# NTC.net
KiCad netlist of a schematic drawn in Altium Designer
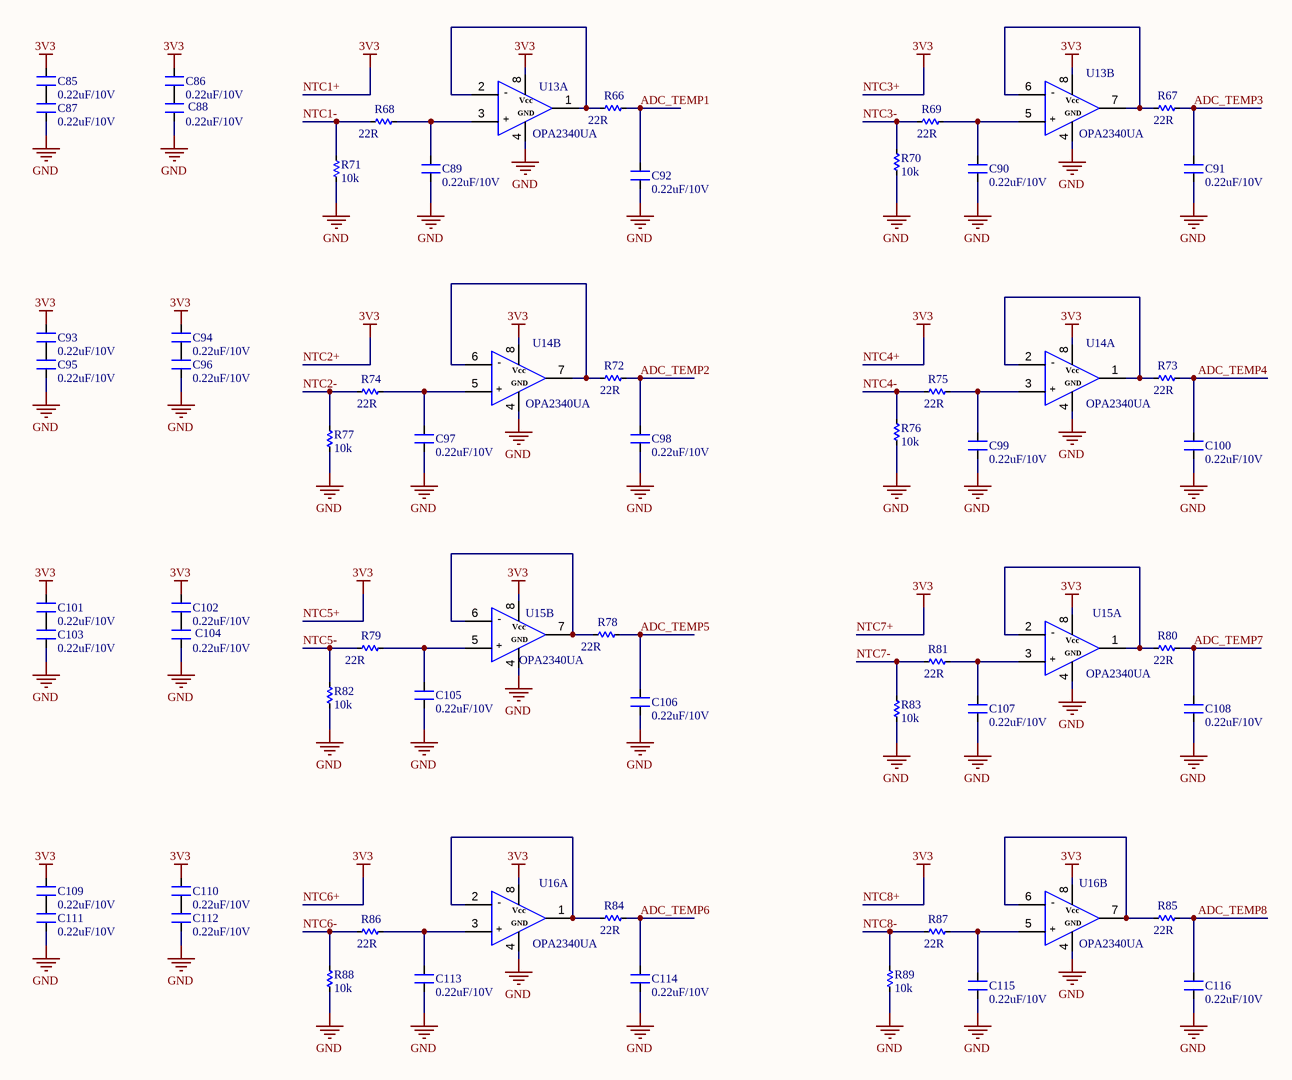
[diagram p0: NTC.SchDoc]

(export (version "E")
  (design (tool "Eeschema 10.0.6"))
  (components
    (comp (ref "C85")
      (value "0.22uF/10V")
      (footprint "CAP_C_1608X80")
      (libsource (lib "EXP_HW_V3") (part "Capacitors"))
    )
    (comp (ref "C86")
      (value "0.22uF/10V")
      (footprint "CAP_C_1608X80")
      (libsource (lib "EXP_HW_V3") (part "Capacitors"))
    )
    (comp (ref "C87")
      (value "0.22uF/10V")
      (footprint "CAP_C_1608X80")
      (libsource (lib "EXP_HW_V3") (part "Capacitors"))
    )
    (comp (ref "C88")
      (value "0.22uF/10V")
      (footprint "CAP_C_1608X80")
      (libsource (lib "EXP_HW_V3") (part "Capacitors"))
    )
    (comp (ref "C89")
      (value "0.22uF/10V")
      (footprint "CAP_C_1608X80")
      (libsource (lib "EXP_HW_V3") (part "Capacitors"))
    )
    (comp (ref "C90")
      (value "0.22uF/10V")
      (footprint "CAP_C_1608X80")
      (libsource (lib "EXP_HW_V3") (part "Capacitors"))
    )
    (comp (ref "C91")
      (value "0.22uF/10V")
      (footprint "CAP_C_1608X80")
      (libsource (lib "EXP_HW_V3") (part "Capacitors"))
    )
    (comp (ref "C92")
      (value "0.22uF/10V")
      (footprint "CAP_C_1608X80")
      (libsource (lib "EXP_HW_V3") (part "Capacitors"))
    )
    (comp (ref "C93")
      (value "0.22uF/10V")
      (footprint "CAP_C_1608X80")
      (libsource (lib "EXP_HW_V3") (part "Capacitors"))
    )
    (comp (ref "C94")
      (value "0.22uF/10V")
      (footprint "CAP_C_1608X80")
      (libsource (lib "EXP_HW_V3") (part "Capacitors"))
    )
    (comp (ref "C95")
      (value "0.22uF/10V")
      (footprint "CAP_C_1608X80")
      (libsource (lib "EXP_HW_V3") (part "Capacitors"))
    )
    (comp (ref "C96")
      (value "0.22uF/10V")
      (footprint "CAP_C_1608X80")
      (libsource (lib "EXP_HW_V3") (part "Capacitors"))
    )
    (comp (ref "C97")
      (value "0.22uF/10V")
      (footprint "CAP_C_1608X80")
      (libsource (lib "EXP_HW_V3") (part "Capacitors"))
    )
    (comp (ref "C98")
      (value "0.22uF/10V")
      (footprint "CAP_C_1608X80")
      (libsource (lib "EXP_HW_V3") (part "Capacitors"))
    )
    (comp (ref "C99")
      (value "0.22uF/10V")
      (footprint "CAP_C_1608X80")
      (libsource (lib "EXP_HW_V3") (part "Capacitors"))
    )
    (comp (ref "C100")
      (value "0.22uF/10V")
      (footprint "CAP_C_1608X80")
      (libsource (lib "EXP_HW_V3") (part "Capacitors"))
    )
    (comp (ref "C101")
      (value "0.22uF/10V")
      (footprint "CAP_C_1608X80")
      (libsource (lib "EXP_HW_V3") (part "Capacitors"))
    )
    (comp (ref "C102")
      (value "0.22uF/10V")
      (footprint "CAP_C_1608X80")
      (libsource (lib "EXP_HW_V3") (part "Capacitors"))
    )
    (comp (ref "C103")
      (value "0.22uF/10V")
      (footprint "CAP_C_1608X80")
      (libsource (lib "EXP_HW_V3") (part "Capacitors"))
    )
    (comp (ref "C104")
      (value "0.22uF/10V")
      (footprint "CAP_C_1608X80")
      (libsource (lib "EXP_HW_V3") (part "Capacitors"))
    )
    (comp (ref "C105")
      (value "0.22uF/10V")
      (footprint "CAP_C_1608X80")
      (libsource (lib "EXP_HW_V3") (part "Capacitors"))
    )
    (comp (ref "C106")
      (value "0.22uF/10V")
      (footprint "CAP_C_1608X80")
      (libsource (lib "EXP_HW_V3") (part "Capacitors"))
    )
    (comp (ref "C107")
      (value "0.22uF/10V")
      (footprint "CAP_C_1608X80")
      (libsource (lib "EXP_HW_V3") (part "Capacitors"))
    )
    (comp (ref "C108")
      (value "0.22uF/10V")
      (footprint "CAP_C_1608X80")
      (libsource (lib "EXP_HW_V3") (part "Capacitors"))
    )
    (comp (ref "C109")
      (value "0.22uF/10V")
      (footprint "CAP_C_1608X80")
      (libsource (lib "EXP_HW_V3") (part "Capacitors"))
    )
    (comp (ref "C110")
      (value "0.22uF/10V")
      (footprint "CAP_C_1608X80")
      (libsource (lib "EXP_HW_V3") (part "Capacitors"))
    )
    (comp (ref "C111")
      (value "0.22uF/10V")
      (footprint "CAP_C_1608X80")
      (libsource (lib "EXP_HW_V3") (part "Capacitors"))
    )
    (comp (ref "C112")
      (value "0.22uF/10V")
      (footprint "CAP_C_1608X80")
      (libsource (lib "EXP_HW_V3") (part "Capacitors"))
    )
    (comp (ref "C113")
      (value "0.22uF/10V")
      (footprint "CAP_C_1608X80")
      (libsource (lib "EXP_HW_V3") (part "Capacitors"))
    )
    (comp (ref "C114")
      (value "0.22uF/10V")
      (footprint "CAP_C_1608X80")
      (libsource (lib "EXP_HW_V3") (part "Capacitors"))
    )
    (comp (ref "C115")
      (value "0.22uF/10V")
      (footprint "CAP_C_1608X80")
      (libsource (lib "EXP_HW_V3") (part "Capacitors"))
    )
    (comp (ref "C116")
      (value "0.22uF/10V")
      (footprint "CAP_C_1608X80")
      (libsource (lib "EXP_HW_V3") (part "Capacitors"))
    )
    (comp (ref "R66")
      (value "22R")
      (footprint "RES_C_1608X60")
      (description "SMD")
      (fields
        (field (name "MANUFACTURER") "Generic Components")
        (field (name "PUBLISHER") "Altium Hobart Technology Centre")
      )
      (libsource (lib "EXP_HW_V3") (part "Res SMD"))
    )
    (comp (ref "R67")
      (value "22R")
      (footprint "RES_C_1608X60")
      (description "SMD")
      (fields
        (field (name "MANUFACTURER") "Generic Components")
        (field (name "PUBLISHER") "Altium Hobart Technology Centre")
      )
      (libsource (lib "EXP_HW_V3") (part "Res SMD"))
    )
    (comp (ref "R68")
      (value "22R")
      (footprint "RES_C_1608X60")
      (description "SMD")
      (fields
        (field (name "MANUFACTURER") "Generic Components")
        (field (name "PUBLISHER") "Altium Hobart Technology Centre")
      )
      (libsource (lib "EXP_HW_V3") (part "Res SMD"))
    )
    (comp (ref "R69")
      (value "22R")
      (footprint "RES_C_1608X60")
      (description "SMD")
      (fields
        (field (name "MANUFACTURER") "Generic Components")
        (field (name "PUBLISHER") "Altium Hobart Technology Centre")
      )
      (libsource (lib "EXP_HW_V3") (part "Res SMD"))
    )
    (comp (ref "R70")
      (value "10k")
      (footprint "RES_C_1608X60")
      (description "SMD")
      (fields
        (field (name "MANUFACTURER") "Generic Components")
        (field (name "PUBLISHER") "Altium Hobart Technology Centre")
      )
      (libsource (lib "EXP_HW_V3") (part "Res SMD"))
    )
    (comp (ref "R71")
      (value "10k")
      (footprint "RES_C_1608X60")
      (description "SMD")
      (fields
        (field (name "MANUFACTURER") "Generic Components")
        (field (name "PUBLISHER") "Altium Hobart Technology Centre")
      )
      (libsource (lib "EXP_HW_V3") (part "Res SMD"))
    )
    (comp (ref "R72")
      (value "22R")
      (footprint "RES_C_1608X60")
      (description "SMD")
      (fields
        (field (name "MANUFACTURER") "Generic Components")
        (field (name "PUBLISHER") "Altium Hobart Technology Centre")
      )
      (libsource (lib "EXP_HW_V3") (part "Res SMD"))
    )
    (comp (ref "R73")
      (value "22R")
      (footprint "RES_C_1608X60")
      (description "SMD")
      (fields
        (field (name "MANUFACTURER") "Generic Components")
        (field (name "PUBLISHER") "Altium Hobart Technology Centre")
      )
      (libsource (lib "EXP_HW_V3") (part "Res SMD"))
    )
    (comp (ref "R74")
      (value "22R")
      (footprint "RES_C_1608X60")
      (description "SMD")
      (fields
        (field (name "MANUFACTURER") "Generic Components")
        (field (name "PUBLISHER") "Altium Hobart Technology Centre")
      )
      (libsource (lib "EXP_HW_V3") (part "Res SMD"))
    )
    (comp (ref "R75")
      (value "22R")
      (footprint "RES_C_1608X60")
      (description "SMD")
      (fields
        (field (name "MANUFACTURER") "Generic Components")
        (field (name "PUBLISHER") "Altium Hobart Technology Centre")
      )
      (libsource (lib "EXP_HW_V3") (part "Res SMD"))
    )
    (comp (ref "R76")
      (value "10k")
      (footprint "RES_C_1608X60")
      (description "SMD")
      (fields
        (field (name "MANUFACTURER") "Generic Components")
        (field (name "PUBLISHER") "Altium Hobart Technology Centre")
      )
      (libsource (lib "EXP_HW_V3") (part "Res SMD"))
    )
    (comp (ref "R77")
      (value "10k")
      (footprint "RES_C_1608X60")
      (description "SMD")
      (fields
        (field (name "MANUFACTURER") "Generic Components")
        (field (name "PUBLISHER") "Altium Hobart Technology Centre")
      )
      (libsource (lib "EXP_HW_V3") (part "Res SMD"))
    )
    (comp (ref "R78")
      (value "22R")
      (footprint "RES_C_1608X60")
      (description "SMD")
      (fields
        (field (name "MANUFACTURER") "Generic Components")
        (field (name "PUBLISHER") "Altium Hobart Technology Centre")
      )
      (libsource (lib "EXP_HW_V3") (part "Res SMD"))
    )
    (comp (ref "R79")
      (value "22R")
      (footprint "RES_C_1608X60")
      (description "SMD")
      (fields
        (field (name "MANUFACTURER") "Generic Components")
        (field (name "PUBLISHER") "Altium Hobart Technology Centre")
      )
      (libsource (lib "EXP_HW_V3") (part "Res SMD"))
    )
    (comp (ref "R80")
      (value "22R")
      (footprint "RES_C_1608X60")
      (description "SMD")
      (fields
        (field (name "MANUFACTURER") "Generic Components")
        (field (name "PUBLISHER") "Altium Hobart Technology Centre")
      )
      (libsource (lib "EXP_HW_V3") (part "Res SMD"))
    )
    (comp (ref "R81")
      (value "22R")
      (footprint "RES_C_1608X60")
      (description "SMD")
      (fields
        (field (name "MANUFACTURER") "Generic Components")
        (field (name "PUBLISHER") "Altium Hobart Technology Centre")
      )
      (libsource (lib "EXP_HW_V3") (part "Res SMD"))
    )
    (comp (ref "R82")
      (value "10k")
      (footprint "RES_C_1608X60")
      (description "SMD")
      (fields
        (field (name "MANUFACTURER") "Generic Components")
        (field (name "PUBLISHER") "Altium Hobart Technology Centre")
      )
      (libsource (lib "EXP_HW_V3") (part "Res SMD"))
    )
    (comp (ref "R83")
      (value "10k")
      (footprint "RES_C_1608X60")
      (description "SMD")
      (fields
        (field (name "MANUFACTURER") "Generic Components")
        (field (name "PUBLISHER") "Altium Hobart Technology Centre")
      )
      (libsource (lib "EXP_HW_V3") (part "Res SMD"))
    )
    (comp (ref "R84")
      (value "22R")
      (footprint "RES_C_1608X60")
      (description "SMD")
      (fields
        (field (name "MANUFACTURER") "Generic Components")
        (field (name "PUBLISHER") "Altium Hobart Technology Centre")
      )
      (libsource (lib "EXP_HW_V3") (part "Res SMD"))
    )
    (comp (ref "R85")
      (value "22R")
      (footprint "RES_C_1608X60")
      (description "SMD")
      (fields
        (field (name "MANUFACTURER") "Generic Components")
        (field (name "PUBLISHER") "Altium Hobart Technology Centre")
      )
      (libsource (lib "EXP_HW_V3") (part "Res SMD"))
    )
    (comp (ref "R86")
      (value "22R")
      (footprint "RES_C_1608X60")
      (description "SMD")
      (fields
        (field (name "MANUFACTURER") "Generic Components")
        (field (name "PUBLISHER") "Altium Hobart Technology Centre")
      )
      (libsource (lib "EXP_HW_V3") (part "Res SMD"))
    )
    (comp (ref "R87")
      (value "22R")
      (footprint "RES_C_1608X60")
      (description "SMD")
      (fields
        (field (name "MANUFACTURER") "Generic Components")
        (field (name "PUBLISHER") "Altium Hobart Technology Centre")
      )
      (libsource (lib "EXP_HW_V3") (part "Res SMD"))
    )
    (comp (ref "R88")
      (value "10k")
      (footprint "RES_C_1608X60")
      (description "SMD")
      (fields
        (field (name "MANUFACTURER") "Generic Components")
        (field (name "PUBLISHER") "Altium Hobart Technology Centre")
      )
      (libsource (lib "EXP_HW_V3") (part "Res SMD"))
    )
    (comp (ref "R89")
      (value "10k")
      (footprint "RES_C_1608X60")
      (description "SMD")
      (fields
        (field (name "MANUFACTURER") "Generic Components")
        (field (name "PUBLISHER") "Altium Hobart Technology Centre")
      )
      (libsource (lib "EXP_HW_V3") (part "Res SMD"))
    )
    (comp (ref "U13") (value "OPA2340UA") (footprint "SO8") (libsource (lib "EXP_HW_V3") (part "OPA2340UA")))
    (comp (ref "U14") (value "OPA2340UA") (footprint "SO8") (libsource (lib "EXP_HW_V3") (part "OPA2340UA")))
    (comp (ref "U15") (value "OPA2340UA") (footprint "SO8") (libsource (lib "EXP_HW_V3") (part "OPA2340UA")))
    (comp (ref "U16") (value "OPA2340UA") (footprint "SO8") (libsource (lib "EXP_HW_V3") (part "OPA2340UA")))
  )
  (nets
    (net (code "1") (name "/ADC_TEMP1") (class "Default")
      (node (ref "C92") (pin "2") (pinfunction "2_2") (pintype "passive"))
      (node (ref "R66") (pin "2") (pinfunction "2_2") (pintype "passive"))
    )
    (net (code "2") (name "/ADC_TEMP2") (class "Default")
      (node (ref "C98") (pin "2") (pinfunction "2_2") (pintype "passive"))
      (node (ref "R72") (pin "2") (pinfunction "2_2") (pintype "passive"))
    )
    (net (code "3") (name "/ADC_TEMP3") (class "Default")
      (node (ref "C91") (pin "2") (pinfunction "2_2") (pintype "passive"))
      (node (ref "R67") (pin "2") (pinfunction "2_2") (pintype "passive"))
    )
    (net (code "4") (name "/ADC_TEMP4") (class "Default")
      (node (ref "C100") (pin "2") (pinfunction "2_2") (pintype "passive"))
      (node (ref "R73") (pin "2") (pinfunction "2_2") (pintype "passive"))
    )
    (net (code "5") (name "/ADC_TEMP5") (class "Default")
      (node (ref "C106") (pin "2") (pinfunction "2_2") (pintype "passive"))
      (node (ref "R78") (pin "2") (pinfunction "2_2") (pintype "passive"))
    )
    (net (code "6") (name "/ADC_TEMP6") (class "Default")
      (node (ref "C114") (pin "2") (pinfunction "2_2") (pintype "passive"))
      (node (ref "R84") (pin "2") (pinfunction "2_2") (pintype "passive"))
    )
    (net (code "7") (name "/ADC_TEMP7") (class "Default")
      (node (ref "C108") (pin "2") (pinfunction "2_2") (pintype "passive"))
      (node (ref "R80") (pin "2") (pinfunction "2_2") (pintype "passive"))
    )
    (net (code "8") (name "/ADC_TEMP8") (class "Default")
      (node (ref "C116") (pin "2") (pinfunction "2_2") (pintype "passive"))
      (node (ref "R85") (pin "2") (pinfunction "2_2") (pintype "passive"))
    )
    (net (code "9") (name "/NTC1-") (class "Default")
      (node (ref "R68") (pin "1") (pinfunction "1_1") (pintype "passive"))
      (node (ref "R71") (pin "1") (pinfunction "1_1") (pintype "passive"))
    )
    (net (code "10") (name "/NTC2-") (class "Default")
      (node (ref "R74") (pin "1") (pinfunction "1_1") (pintype "passive"))
      (node (ref "R77") (pin "1") (pinfunction "1_1") (pintype "passive"))
    )
    (net (code "11") (name "/NTC3-") (class "Default")
      (node (ref "R69") (pin "1") (pinfunction "1_1") (pintype "passive"))
      (node (ref "R70") (pin "1") (pinfunction "1_1") (pintype "passive"))
    )
    (net (code "12") (name "/NTC4-") (class "Default")
      (node (ref "R75") (pin "1") (pinfunction "1_1") (pintype "passive"))
      (node (ref "R76") (pin "1") (pinfunction "1_1") (pintype "passive"))
    )
    (net (code "13") (name "/NTC5-") (class "Default")
      (node (ref "R79") (pin "1") (pinfunction "1_1") (pintype "passive"))
      (node (ref "R82") (pin "1") (pinfunction "1_1") (pintype "passive"))
    )
    (net (code "14") (name "/NTC6-") (class "Default")
      (node (ref "R86") (pin "1") (pinfunction "1_1") (pintype "passive"))
      (node (ref "R88") (pin "1") (pinfunction "1_1") (pintype "passive"))
    )
    (net (code "15") (name "/NTC7-") (class "Default")
      (node (ref "R81") (pin "1") (pinfunction "1_1") (pintype "passive"))
      (node (ref "R83") (pin "1") (pinfunction "1_1") (pintype "passive"))
    )
    (net (code "16") (name "/NTC8-") (class "Default")
      (node (ref "R87") (pin "1") (pinfunction "1_1") (pintype "passive"))
      (node (ref "R89") (pin "1") (pinfunction "1_1") (pintype "passive"))
    )
    (net (code "17") (name "3V3") (class "Default")
      (node (ref "C101") (pin "2") (pinfunction "2_2") (pintype "passive"))
      (node (ref "C102") (pin "2") (pinfunction "2_2") (pintype "passive"))
      (node (ref "C109") (pin "2") (pinfunction "2_2") (pintype "passive"))
      (node (ref "C110") (pin "2") (pinfunction "2_2") (pintype "passive"))
      (node (ref "C85") (pin "2") (pinfunction "2_2") (pintype "passive"))
      (node (ref "C86") (pin "2") (pinfunction "2_2") (pintype "passive"))
      (node (ref "C93") (pin "2") (pinfunction "2_2") (pintype "passive"))
      (node (ref "C94") (pin "2") (pinfunction "2_2") (pintype "passive"))
      (node (ref "U13") (pin "8") (pinfunction "8_8") (pintype "passive"))
      (node (ref "U14") (pin "8") (pinfunction "8_8") (pintype "passive"))
      (node (ref "U15") (pin "8") (pinfunction "8_8") (pintype "passive"))
      (node (ref "U16") (pin "8") (pinfunction "8_8") (pintype "passive"))
    )
    (net (code "18") (name "GND") (class "Default")
      (node (ref "C100") (pin "1") (pinfunction "1_1") (pintype "passive"))
      (node (ref "C103") (pin "1") (pinfunction "1_1") (pintype "passive"))
      (node (ref "C104") (pin "1") (pinfunction "1_1") (pintype "passive"))
      (node (ref "C105") (pin "1") (pinfunction "1_1") (pintype "passive"))
      (node (ref "C106") (pin "1") (pinfunction "1_1") (pintype "passive"))
      (node (ref "C107") (pin "1") (pinfunction "1_1") (pintype "passive"))
      (node (ref "C108") (pin "1") (pinfunction "1_1") (pintype "passive"))
      (node (ref "C111") (pin "1") (pinfunction "1_1") (pintype "passive"))
      (node (ref "C112") (pin "1") (pinfunction "1_1") (pintype "passive"))
      (node (ref "C113") (pin "1") (pinfunction "1_1") (pintype "passive"))
      (node (ref "C114") (pin "1") (pinfunction "1_1") (pintype "passive"))
      (node (ref "C115") (pin "1") (pinfunction "1_1") (pintype "passive"))
      (node (ref "C116") (pin "1") (pinfunction "1_1") (pintype "passive"))
      (node (ref "C87") (pin "1") (pinfunction "1_1") (pintype "passive"))
      (node (ref "C88") (pin "1") (pinfunction "1_1") (pintype "passive"))
      (node (ref "C89") (pin "1") (pinfunction "1_1") (pintype "passive"))
      (node (ref "C90") (pin "1") (pinfunction "1_1") (pintype "passive"))
      (node (ref "C91") (pin "1") (pinfunction "1_1") (pintype "passive"))
      (node (ref "C92") (pin "1") (pinfunction "1_1") (pintype "passive"))
      (node (ref "C95") (pin "1") (pinfunction "1_1") (pintype "passive"))
      (node (ref "C96") (pin "1") (pinfunction "1_1") (pintype "passive"))
      (node (ref "C97") (pin "1") (pinfunction "1_1") (pintype "passive"))
      (node (ref "C98") (pin "1") (pinfunction "1_1") (pintype "passive"))
      (node (ref "C99") (pin "1") (pinfunction "1_1") (pintype "passive"))
      (node (ref "R70") (pin "2") (pinfunction "2_2") (pintype "passive"))
      (node (ref "R71") (pin "2") (pinfunction "2_2") (pintype "passive"))
      (node (ref "R76") (pin "2") (pinfunction "2_2") (pintype "passive"))
      (node (ref "R77") (pin "2") (pinfunction "2_2") (pintype "passive"))
      (node (ref "R82") (pin "2") (pinfunction "2_2") (pintype "passive"))
      (node (ref "R83") (pin "2") (pinfunction "2_2") (pintype "passive"))
      (node (ref "R88") (pin "2") (pinfunction "2_2") (pintype "passive"))
      (node (ref "R89") (pin "2") (pinfunction "2_2") (pintype "passive"))
      (node (ref "U13") (pin "4") (pinfunction "4_4") (pintype "passive"))
      (node (ref "U14") (pin "4") (pinfunction "4_4") (pintype "passive"))
      (node (ref "U15") (pin "4") (pinfunction "4_4") (pintype "passive"))
      (node (ref "U16") (pin "4") (pinfunction "4_4") (pintype "passive"))
    )
    (net (code "19") (name "Net-(C85-Pad1)") (class "Default")
      (node (ref "C85") (pin "1") (pinfunction "1_1") (pintype "passive"))
      (node (ref "C87") (pin "2") (pinfunction "2_2") (pintype "passive"))
    )
    (net (code "20") (name "Net-(C86-Pad1)") (class "Default")
      (node (ref "C86") (pin "1") (pinfunction "1_1") (pintype "passive"))
      (node (ref "C88") (pin "2") (pinfunction "2_2") (pintype "passive"))
    )
    (net (code "21") (name "Net-(C89-Pad2)") (class "Default")
      (node (ref "C89") (pin "2") (pinfunction "2_2") (pintype "passive"))
      (node (ref "R68") (pin "2") (pinfunction "2_2") (pintype "passive"))
      (node (ref "U13") (pin "3") (pinfunction "3_3") (pintype "passive"))
    )
    (net (code "22") (name "Net-(C90-Pad2)") (class "Default")
      (node (ref "C90") (pin "2") (pinfunction "2_2") (pintype "passive"))
      (node (ref "R69") (pin "2") (pinfunction "2_2") (pintype "passive"))
      (node (ref "U13") (pin "5") (pinfunction "5_5") (pintype "passive"))
    )
    (net (code "23") (name "Net-(C93-Pad1)") (class "Default")
      (node (ref "C93") (pin "1") (pinfunction "1_1") (pintype "passive"))
      (node (ref "C95") (pin "2") (pinfunction "2_2") (pintype "passive"))
    )
    (net (code "24") (name "Net-(C94-Pad1)") (class "Default")
      (node (ref "C94") (pin "1") (pinfunction "1_1") (pintype "passive"))
      (node (ref "C96") (pin "2") (pinfunction "2_2") (pintype "passive"))
    )
    (net (code "25") (name "Net-(C97-Pad2)") (class "Default")
      (node (ref "C97") (pin "2") (pinfunction "2_2") (pintype "passive"))
      (node (ref "R74") (pin "2") (pinfunction "2_2") (pintype "passive"))
      (node (ref "U14") (pin "5") (pinfunction "5_5") (pintype "passive"))
    )
    (net (code "26") (name "Net-(C99-Pad2)") (class "Default")
      (node (ref "C99") (pin "2") (pinfunction "2_2") (pintype "passive"))
      (node (ref "R75") (pin "2") (pinfunction "2_2") (pintype "passive"))
      (node (ref "U14") (pin "3") (pinfunction "3_3") (pintype "passive"))
    )
    (net (code "27") (name "Net-(C101-Pad1)") (class "Default")
      (node (ref "C101") (pin "1") (pinfunction "1_1") (pintype "passive"))
      (node (ref "C103") (pin "2") (pinfunction "2_2") (pintype "passive"))
    )
    (net (code "28") (name "Net-(C102-Pad1)") (class "Default")
      (node (ref "C102") (pin "1") (pinfunction "1_1") (pintype "passive"))
      (node (ref "C104") (pin "2") (pinfunction "2_2") (pintype "passive"))
    )
    (net (code "29") (name "Net-(C105-Pad2)") (class "Default")
      (node (ref "C105") (pin "2") (pinfunction "2_2") (pintype "passive"))
      (node (ref "R79") (pin "2") (pinfunction "2_2") (pintype "passive"))
      (node (ref "U15") (pin "5") (pinfunction "5_5") (pintype "passive"))
    )
    (net (code "30") (name "Net-(C107-Pad2)") (class "Default")
      (node (ref "C107") (pin "2") (pinfunction "2_2") (pintype "passive"))
      (node (ref "R81") (pin "2") (pinfunction "2_2") (pintype "passive"))
      (node (ref "U15") (pin "3") (pinfunction "3_3") (pintype "passive"))
    )
    (net (code "31") (name "Net-(C109-Pad1)") (class "Default")
      (node (ref "C109") (pin "1") (pinfunction "1_1") (pintype "passive"))
      (node (ref "C111") (pin "2") (pinfunction "2_2") (pintype "passive"))
    )
    (net (code "32") (name "Net-(C110-Pad1)") (class "Default")
      (node (ref "C110") (pin "1") (pinfunction "1_1") (pintype "passive"))
      (node (ref "C112") (pin "2") (pinfunction "2_2") (pintype "passive"))
    )
    (net (code "33") (name "Net-(C113-Pad2)") (class "Default")
      (node (ref "C113") (pin "2") (pinfunction "2_2") (pintype "passive"))
      (node (ref "R86") (pin "2") (pinfunction "2_2") (pintype "passive"))
      (node (ref "U16") (pin "3") (pinfunction "3_3") (pintype "passive"))
    )
    (net (code "34") (name "Net-(C115-Pad2)") (class "Default")
      (node (ref "C115") (pin "2") (pinfunction "2_2") (pintype "passive"))
      (node (ref "R87") (pin "2") (pinfunction "2_2") (pintype "passive"))
      (node (ref "U16") (pin "5") (pinfunction "5_5") (pintype "passive"))
    )
    (net (code "35") (name "Net-(R66-Pad1)") (class "Default")
      (node (ref "R66") (pin "1") (pinfunction "1_1") (pintype "passive"))
      (node (ref "U13") (pin "1") (pinfunction "1_1") (pintype "passive"))
      (node (ref "U13") (pin "2") (pinfunction "2_2") (pintype "passive"))
    )
    (net (code "36") (name "Net-(R67-Pad1)") (class "Default")
      (node (ref "R67") (pin "1") (pinfunction "1_1") (pintype "passive"))
      (node (ref "U13") (pin "6") (pinfunction "6_6") (pintype "passive"))
      (node (ref "U13") (pin "7") (pinfunction "7_7") (pintype "passive"))
    )
    (net (code "37") (name "Net-(R72-Pad1)") (class "Default")
      (node (ref "R72") (pin "1") (pinfunction "1_1") (pintype "passive"))
      (node (ref "U14") (pin "6") (pinfunction "6_6") (pintype "passive"))
      (node (ref "U14") (pin "7") (pinfunction "7_7") (pintype "passive"))
    )
    (net (code "38") (name "Net-(R73-Pad1)") (class "Default")
      (node (ref "R73") (pin "1") (pinfunction "1_1") (pintype "passive"))
      (node (ref "U14") (pin "1") (pinfunction "1_1") (pintype "passive"))
      (node (ref "U14") (pin "2") (pinfunction "2_2") (pintype "passive"))
    )
    (net (code "39") (name "Net-(R78-Pad1)") (class "Default")
      (node (ref "R78") (pin "1") (pinfunction "1_1") (pintype "passive"))
      (node (ref "U15") (pin "6") (pinfunction "6_6") (pintype "passive"))
      (node (ref "U15") (pin "7") (pinfunction "7_7") (pintype "passive"))
    )
    (net (code "40") (name "Net-(R80-Pad1)") (class "Default")
      (node (ref "R80") (pin "1") (pinfunction "1_1") (pintype "passive"))
      (node (ref "U15") (pin "1") (pinfunction "1_1") (pintype "passive"))
      (node (ref "U15") (pin "2") (pinfunction "2_2") (pintype "passive"))
    )
    (net (code "41") (name "Net-(R84-Pad1)") (class "Default")
      (node (ref "R84") (pin "1") (pinfunction "1_1") (pintype "passive"))
      (node (ref "U16") (pin "1") (pinfunction "1_1") (pintype "passive"))
      (node (ref "U16") (pin "2") (pinfunction "2_2") (pintype "passive"))
    )
    (net (code "42") (name "Net-(R85-Pad1)") (class "Default")
      (node (ref "R85") (pin "1") (pinfunction "1_1") (pintype "passive"))
      (node (ref "U16") (pin "6") (pinfunction "6_6") (pintype "passive"))
      (node (ref "U16") (pin "7") (pinfunction "7_7") (pintype "passive"))
    )
  )
)
